# HC-05_BlueTooth.net
KiCad netlist of a schematic drawn in Altium Designer
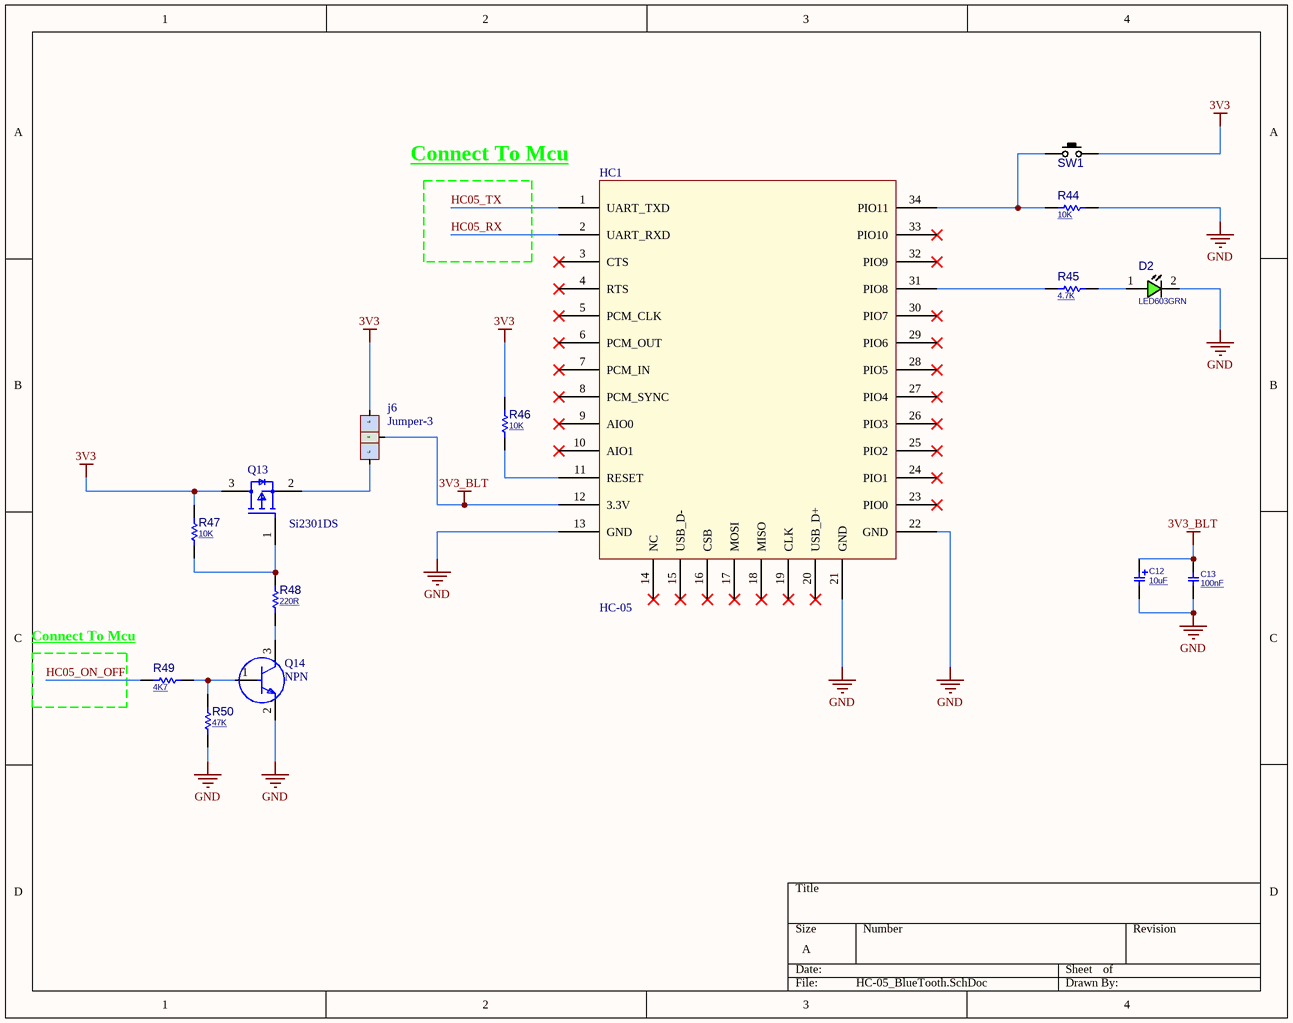
[diagram p0: HC-05_BlueTooth.SchDoc]

(export (version "E")
  (design (tool "Eeschema 10.0.6"))
  (components
    (comp (ref "C12")
      (value "10uF")
      (footprint "C_TN_3216")
      (description "CAP, SMD, TAN,")
      (fields (field (name "Comment") "4.7uF"))
      (libsource (lib "passive_smd") (part "CAP_SMD_TAN_3216"))
    )
    (comp (ref "C13")
      (value "100nF")
      (footprint "C0603")
      (description "CAP, MLCC, -F, -V, MATERIAL, -%, 0201")
      (fields (field (name "MANF_P#") "MANF_PART#"))
      (libsource (lib "passive_smd") (part "CAP_SMD_MLCC_0603"))
    )
    (comp (ref "D2")
      (value "LED603GRN")
      (footprint "LED0603GRN")
      (description "LED, SMD, 0603, GREEN")
      (fields (field (name "MANF") "Kingbright") (field (name "MANF_P#") "APT1608SGC"))
      (libsource (lib "led(diode)") (part "LED_SMD_0603_GRN"))
    )
    (comp (ref "HC1") (value "HC-05") (footprint "HC-05") (libsource (lib "Module") (part "HC-05")))
    (comp (ref "j6") (value "Jumper-3") (footprint "jumper-3") (libsource (lib "jumper") (part "Jumper-3")))
    (comp (ref "Q13")
      (value "Si2301DS")
      (footprint "FP-S-03946-IPC_A")
      (description "P-Channel 1.25-W, 2.5-V MOSFET")
      (fields
        (field (name "MANUFACTURER") "Vishay")
        (field (name "OCTOPART") "https://octopart.com/si2303cds-t1-ge3-vishay-43171446")
      )
      (libsource (lib "si2301-pCH-mosfet") (part "Si2301DS"))
    )
    (comp (ref "Q14")
      (value "NPN")
      (footprint "FP-SOT23-IPC_A")
      (libsource (lib "NPN-SOT-23") (part "CMP-2000-04931-2"))
    )
    (comp (ref "R44")
      (value "10K")
      (footprint "R0603")
      (description "RESISTOR, SMD")
      (libsource (lib "passive_smd") (part "RES_SMD"))
    )
    (comp (ref "R45")
      (value "4.7K")
      (footprint "R0603")
      (description "RESISTOR, SMD")
      (libsource (lib "passive_smd") (part "RES_SMD"))
    )
    (comp (ref "R46")
      (value "10K")
      (footprint "R0603")
      (description "RESISTOR, SMD")
      (libsource (lib "passive_smd") (part "RES_SMD"))
    )
    (comp (ref "R47")
      (value "10K")
      (footprint "R0603")
      (description "RESISTOR, SMD")
      (libsource (lib "passive_smd") (part "RES_SMD"))
    )
    (comp (ref "R48")
      (value "220R")
      (footprint "R0603")
      (description "RESISTOR, SMD")
      (libsource (lib "passive_smd") (part "RES_SMD"))
    )
    (comp (ref "R49")
      (value "4K7")
      (footprint "R0603")
      (description "RESISTOR, SMD")
      (libsource (lib "passive_smd") (part "RES_SMD"))
    )
    (comp (ref "R50")
      (value "47K")
      (footprint "R0603")
      (description "RESISTOR, SMD")
      (libsource (lib "passive_smd") (part "RES_SMD"))
    )
    (comp (ref "SW1")
      (value "PUSHBUTTON")
      (footprint "SWPBS_SPST_6X3X5")
      (description "SWITCH, PUSH BUTTON, TACTILE, SMD, SPST, 6X3.5X5mm")
      (fields (field (name "MANF") "ALPS") (field (name "MANF_P#") "SKQMBBE010"))
      (libsource (lib "switch_tact_PUSHB") (part "SWPBS_SPST_6X3X5"))
    )
  )
  (nets
    (net (code "1") (name "/HC05_ON_OFF") (class "Default")
      (node (ref "R49") (pin "1") (pinfunction "1_1") (pintype "passive"))
    )
    (net (code "2") (name "/HC05_RX") (class "Default")
      (node (ref "HC1") (pin "2") (pinfunction "UART_RXD_2") (pintype "passive"))
    )
    (net (code "3") (name "/HC05_TX") (class "Default")
      (node (ref "HC1") (pin "1") (pinfunction "UART_TXD_1") (pintype "passive"))
    )
    (net (code "4") (name "3V3") (class "Default")
      (node (ref "Q13") (pin "3") (pinfunction "D_3") (pintype "passive"))
      (node (ref "R46") (pin "1") (pinfunction "1_1") (pintype "passive"))
      (node (ref "R47") (pin "2") (pinfunction "2_2") (pintype "passive"))
      (node (ref "SW1") (pin "2") (pinfunction "P3_2") (pintype "passive"))
      (node (ref "j6") (pin "1") (pinfunction "1_1") (pintype "passive"))
    )
    (net (code "5") (name "3V3_BLT") (class "Default")
      (node (ref "C12") (pin "1") (pinfunction "1_1") (pintype "passive"))
      (node (ref "C13") (pin "2") (pinfunction "2_2") (pintype "passive"))
      (node (ref "HC1") (pin "12") (pinfunction "3.3V_12") (pintype "passive"))
      (node (ref "j6") (pin "2") (pinfunction "2_2") (pintype "passive"))
    )
    (net (code "6") (name "GND") (class "Default")
      (node (ref "C12") (pin "2") (pinfunction "2_2") (pintype "passive"))
      (node (ref "C13") (pin "1") (pinfunction "1_1") (pintype "passive"))
      (node (ref "D2") (pin "2") (pinfunction "CATHODE_2") (pintype "passive"))
      (node (ref "HC1") (pin "13") (pinfunction "GND_13") (pintype "passive"))
      (node (ref "HC1") (pin "21") (pinfunction "GND_21") (pintype "passive"))
      (node (ref "HC1") (pin "22") (pinfunction "GND_22") (pintype "passive"))
      (node (ref "Q14") (pin "2") (pinfunction "E_2") (pintype "passive"))
      (node (ref "R44") (pin "1") (pinfunction "1_1") (pintype "passive"))
      (node (ref "R50") (pin "1") (pinfunction "1_1") (pintype "passive"))
    )
    (net (code "7") (name "Net-(D2-ANODE)") (class "Default")
      (node (ref "D2") (pin "1") (pinfunction "ANODE_1") (pintype "passive"))
      (node (ref "R45") (pin "1") (pinfunction "1_1") (pintype "passive"))
    )
    (net (code "8") (name "Net-(HC1-PIO8)") (class "Default")
      (node (ref "HC1") (pin "31") (pinfunction "PIO8_31") (pintype "passive"))
      (node (ref "R45") (pin "2") (pinfunction "2_2") (pintype "passive"))
    )
    (net (code "9") (name "Net-(HC1-PIO11)") (class "Default")
      (node (ref "HC1") (pin "34") (pinfunction "PIO11_34") (pintype "passive"))
      (node (ref "R44") (pin "2") (pinfunction "2_2") (pintype "passive"))
      (node (ref "SW1") (pin "1") (pinfunction "P1_1") (pintype "passive"))
    )
    (net (code "10") (name "Net-(HC1-RESET)") (class "Default")
      (node (ref "HC1") (pin "11") (pinfunction "RESET_11") (pintype "passive"))
      (node (ref "R46") (pin "2") (pinfunction "2_2") (pintype "passive"))
    )
    (net (code "11") (name "Net-(Q13-G)") (class "Default")
      (node (ref "Q13") (pin "1") (pinfunction "G_1") (pintype "passive"))
      (node (ref "R47") (pin "1") (pinfunction "1_1") (pintype "passive"))
      (node (ref "R48") (pin "2") (pinfunction "2_2") (pintype "passive"))
    )
    (net (code "12") (name "Net-(Q13-S)") (class "Default")
      (node (ref "Q13") (pin "2") (pinfunction "S_2") (pintype "passive"))
      (node (ref "j6") (pin "3") (pinfunction "3_3") (pintype "passive"))
    )
    (net (code "13") (name "Net-(Q14-B)") (class "Default")
      (node (ref "Q14") (pin "1") (pinfunction "B_1") (pintype "passive"))
      (node (ref "R49") (pin "2") (pinfunction "2_2") (pintype "passive"))
      (node (ref "R50") (pin "2") (pinfunction "2_2") (pintype "passive"))
    )
    (net (code "14") (name "Net-(Q14-C)") (class "Default")
      (node (ref "Q14") (pin "3") (pinfunction "C_3") (pintype "passive"))
      (node (ref "R48") (pin "1") (pinfunction "1_1") (pintype "passive"))
    )
    (net (code "15") (name "unconnected-(HC1-AIO0-Pad9)") (class "Default")
      (node (ref "HC1") (pin "9") (pinfunction "AIO0_9") (pintype "passive+no_connect"))
    )
    (net (code "16") (name "unconnected-(HC1-AIO1-Pad10)") (class "Default")
      (node (ref "HC1") (pin "10") (pinfunction "AIO1_10") (pintype "passive+no_connect"))
    )
    (net (code "17") (name "unconnected-(HC1-CLK-Pad19)") (class "Default")
      (node (ref "HC1") (pin "19") (pinfunction "CLK_19") (pintype "passive+no_connect"))
    )
    (net (code "18") (name "unconnected-(HC1-CSB-Pad16)") (class "Default")
      (node (ref "HC1") (pin "16") (pinfunction "CSB_16") (pintype "passive+no_connect"))
    )
    (net (code "19") (name "unconnected-(HC1-CTS-Pad3)") (class "Default")
      (node (ref "HC1") (pin "3") (pinfunction "CTS_3") (pintype "passive+no_connect"))
    )
    (net (code "20") (name "unconnected-(HC1-MISO-Pad18)") (class "Default")
      (node (ref "HC1") (pin "18") (pinfunction "MISO_18") (pintype "passive+no_connect"))
    )
    (net (code "21") (name "unconnected-(HC1-MOSI-Pad17)") (class "Default")
      (node (ref "HC1") (pin "17") (pinfunction "MOSI_17") (pintype "passive+no_connect"))
    )
    (net (code "22") (name "unconnected-(HC1-NC-Pad14)") (class "Default")
      (node (ref "HC1") (pin "14") (pinfunction "NC_14") (pintype "passive+no_connect"))
    )
    (net (code "23") (name "unconnected-(HC1-PCM_CLK-Pad5)") (class "Default")
      (node (ref "HC1") (pin "5") (pinfunction "PCM_CLK_5") (pintype "passive+no_connect"))
    )
    (net (code "24") (name "unconnected-(HC1-PCM_IN-Pad7)") (class "Default")
      (node (ref "HC1") (pin "7") (pinfunction "PCM_IN_7") (pintype "passive+no_connect"))
    )
    (net (code "25") (name "unconnected-(HC1-PCM_OUT-Pad6)") (class "Default")
      (node (ref "HC1") (pin "6") (pinfunction "PCM_OUT_6") (pintype "passive+no_connect"))
    )
    (net (code "26") (name "unconnected-(HC1-PCM_SYNC-Pad8)") (class "Default")
      (node (ref "HC1") (pin "8") (pinfunction "PCM_SYNC_8") (pintype "passive+no_connect"))
    )
    (net (code "27") (name "unconnected-(HC1-PIO0-Pad23)") (class "Default")
      (node (ref "HC1") (pin "23") (pinfunction "PIO0_23") (pintype "passive+no_connect"))
    )
    (net (code "28") (name "unconnected-(HC1-PIO1-Pad24)") (class "Default")
      (node (ref "HC1") (pin "24") (pinfunction "PIO1_24") (pintype "passive+no_connect"))
    )
    (net (code "29") (name "unconnected-(HC1-PIO2-Pad25)") (class "Default")
      (node (ref "HC1") (pin "25") (pinfunction "PIO2_25") (pintype "passive+no_connect"))
    )
    (net (code "30") (name "unconnected-(HC1-PIO3-Pad26)") (class "Default")
      (node (ref "HC1") (pin "26") (pinfunction "PIO3_26") (pintype "passive+no_connect"))
    )
    (net (code "31") (name "unconnected-(HC1-PIO4-Pad27)") (class "Default")
      (node (ref "HC1") (pin "27") (pinfunction "PIO4_27") (pintype "passive+no_connect"))
    )
    (net (code "32") (name "unconnected-(HC1-PIO5-Pad28)") (class "Default")
      (node (ref "HC1") (pin "28") (pinfunction "PIO5_28") (pintype "passive+no_connect"))
    )
    (net (code "33") (name "unconnected-(HC1-PIO6-Pad29)") (class "Default")
      (node (ref "HC1") (pin "29") (pinfunction "PIO6_29") (pintype "passive+no_connect"))
    )
    (net (code "34") (name "unconnected-(HC1-PIO7-Pad30)") (class "Default")
      (node (ref "HC1") (pin "30") (pinfunction "PIO7_30") (pintype "passive+no_connect"))
    )
    (net (code "35") (name "unconnected-(HC1-PIO9-Pad32)") (class "Default")
      (node (ref "HC1") (pin "32") (pinfunction "PIO9_32") (pintype "passive+no_connect"))
    )
    (net (code "36") (name "unconnected-(HC1-PIO10-Pad33)") (class "Default")
      (node (ref "HC1") (pin "33") (pinfunction "PIO10_33") (pintype "passive+no_connect"))
    )
    (net (code "37") (name "unconnected-(HC1-RTS-Pad4)") (class "Default")
      (node (ref "HC1") (pin "4") (pinfunction "RTS_4") (pintype "passive+no_connect"))
    )
    (net (code "38") (name "unconnected-(HC1-USB_D+-Pad20)") (class "Default")
      (node (ref "HC1") (pin "20") (pinfunction "USB_D+_20") (pintype "passive+no_connect"))
    )
    (net (code "39") (name "unconnected-(HC1-USB_D--Pad15)") (class "Default")
      (node (ref "HC1") (pin "15") (pinfunction "USB_D-_15") (pintype "passive+no_connect"))
    )
  )
)
